# schematic.net
KiCad netlist of a schematic drawn in EAGLE
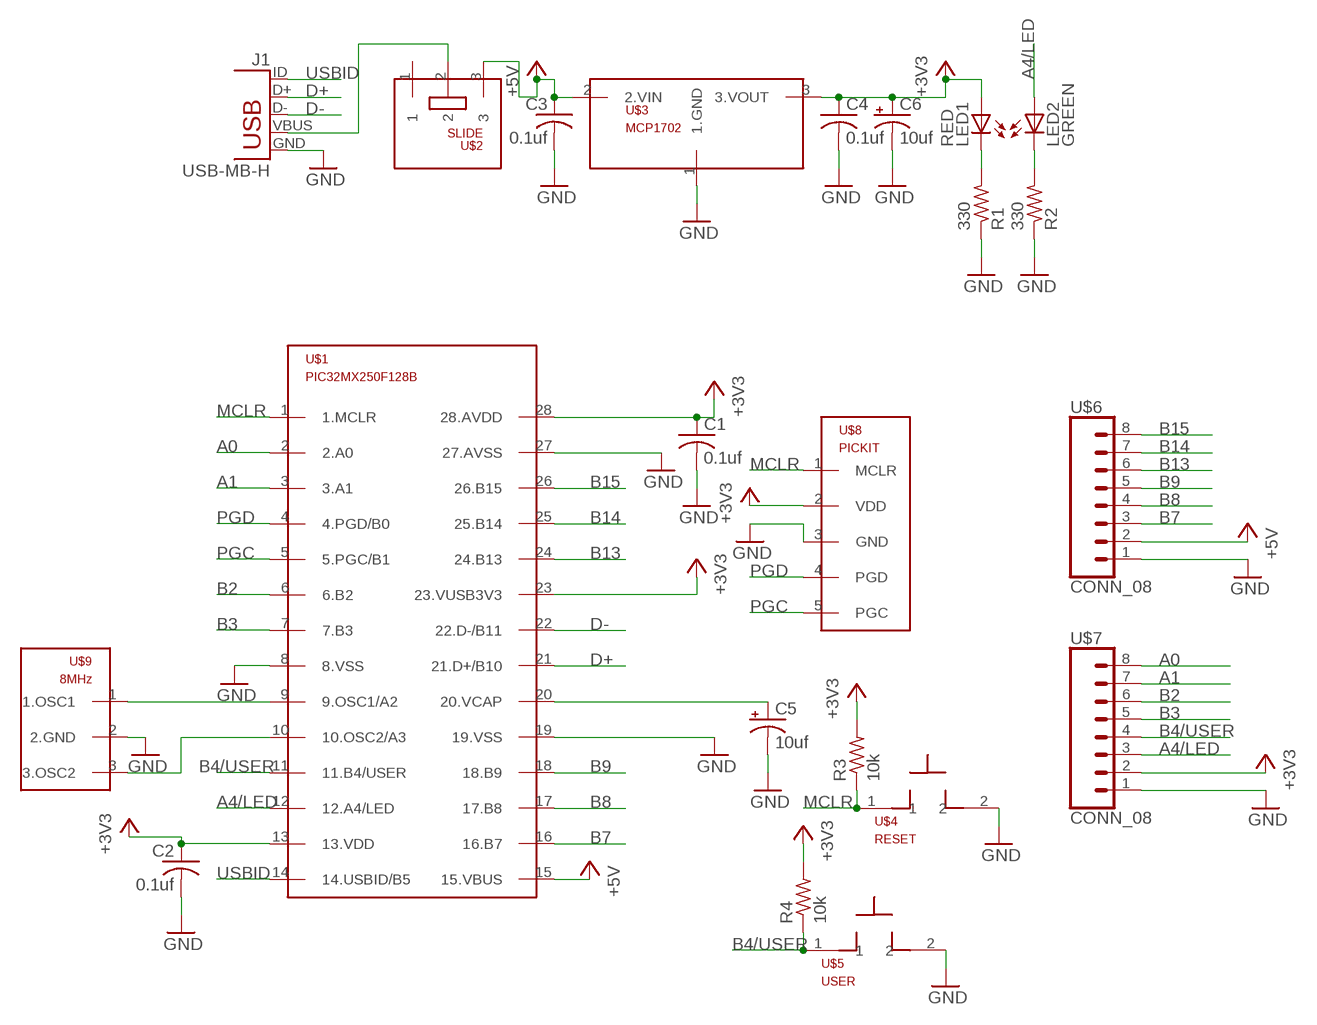
[diagram p0: schematic, sheet 1]

(export (version "E")
  (design (tool "Eeschema 10.0.6"))
  (components
    (comp (ref "C1")
      (value "0.1uf")
      (footprint "eagle-import:C025-025X050")
      (libsource (lib "eagle-import") (part "C-US025-025X050"))
    )
    (comp (ref "C2")
      (value "0.1uf")
      (footprint "eagle-import:C025-025X050")
      (libsource (lib "eagle-import") (part "C-US025-025X050"))
    )
    (comp (ref "C3")
      (value "0.1uf")
      (footprint "eagle-import:C025-025X050")
      (libsource (lib "eagle-import") (part "C-US025-025X050"))
    )
    (comp (ref "C4")
      (value "0.1uf")
      (footprint "eagle-import:C025-025X050")
      (libsource (lib "eagle-import") (part "C-US025-025X050"))
    )
    (comp (ref "C5")
      (value "10uf")
      (footprint "eagle-import:B45181B")
      (libsource (lib "eagle-import") (part "CPOL-USB45181B"))
    )
    (comp (ref "C6")
      (value "10uf")
      (footprint "eagle-import:B45181B")
      (libsource (lib "eagle-import") (part "CPOL-USB45181B"))
    )
    (comp (ref "J1")
      (value "USB-MB-H")
      (footprint "eagle-import:USB-MB-H")
      (libsource (lib "eagle-import") (part "USB-MB-H"))
    )
    (comp (ref "LED1")
      (value "RED")
      (footprint "eagle-import:LED3MM")
      (libsource (lib "eagle-import") (part "LED3MM"))
    )
    (comp (ref "LED2")
      (value "GREEN")
      (footprint "eagle-import:LED3MM")
      (libsource (lib "eagle-import") (part "LED3MM"))
    )
    (comp (ref "R1")
      (value "330")
      (footprint "eagle-import:0207_10")
      (libsource (lib "eagle-import") (part "R-US_0207/10"))
    )
    (comp (ref "R2")
      (value "330")
      (footprint "eagle-import:0207_10")
      (libsource (lib "eagle-import") (part "R-US_0207/10"))
    )
    (comp (ref "R3")
      (value "10k")
      (footprint "eagle-import:0207_10")
      (libsource (lib "eagle-import") (part "R-US_0207/10"))
    )
    (comp (ref "R4")
      (value "10k")
      (footprint "eagle-import:0207_10")
      (libsource (lib "eagle-import") (part "R-US_0207/10"))
    )
    (comp (ref "U$1")
      (value "PIC32MX250F128B")
      (footprint "eagle-import:DIL28-3")
      (libsource (lib "eagle-import") (part "PIC32MX250F128B"))
    )
    (comp (ref "U$2")
      (value "SLIDE")
      (footprint "eagle-import:SLIDE")
      (libsource (lib "eagle-import") (part "SLIDE"))
    )
    (comp (ref "U$3")
      (value "MCP1702")
      (footprint "eagle-import:TO92")
      (libsource (lib "eagle-import") (part "MCP1702"))
    )
    (comp (ref "U$4")
      (value "RESET")
      (footprint "eagle-import:PB")
      (libsource (lib "eagle-import") (part "PB"))
    )
    (comp (ref "U$5")
      (value "USER")
      (footprint "eagle-import:PB")
      (libsource (lib "eagle-import") (part "PB"))
    )
    (comp (ref "U$6")
      (value "CONN_08")
      (footprint "eagle-import:1X08")
      (libsource (lib "eagle-import") (part "CONN_08"))
    )
    (comp (ref "U$7")
      (value "CONN_08")
      (footprint "eagle-import:1X08")
      (libsource (lib "eagle-import") (part "CONN_08"))
    )
    (comp (ref "U$8")
      (value "PICKIT")
      (footprint "eagle-import:1X05")
      (libsource (lib "eagle-import") (part "PICKIT"))
    )
    (comp (ref "U$9")
      (value "8MHz")
      (footprint "eagle-import:OSC")
      (libsource (lib "eagle-import") (part "OSC"))
    )
  )
  (nets
    (net (code "1") (name "+3V3") (class "Default")
      (node (ref "C1") (pin "1") (pinfunction "1_1") (pintype "passive"))
      (node (ref "C2") (pin "1") (pinfunction "1_1") (pintype "passive"))
      (node (ref "C4") (pin "1") (pinfunction "1_1") (pintype "passive"))
      (node (ref "C6") (pin "+") (pinfunction "+_+") (pintype "passive"))
      (node (ref "LED1") (pin "A") (pinfunction "A_A") (pintype "passive"))
      (node (ref "R3") (pin "2") (pinfunction "2_2") (pintype "passive"))
      (node (ref "R4") (pin "2") (pinfunction "2_2") (pintype "passive"))
      (node (ref "U$1") (pin "13") (pinfunction "13.VDD_13") (pintype "bidirectional"))
      (node (ref "U$1") (pin "23") (pinfunction "23.VUSB3V3_23") (pintype "bidirectional"))
      (node (ref "U$1") (pin "28") (pinfunction "28.AVDD_28") (pintype "bidirectional"))
      (node (ref "U$3") (pin "3") (pinfunction "3.VOUT_3") (pintype "bidirectional"))
      (node (ref "U$7") (pin "2") (pinfunction "2_2") (pintype "passive"))
      (node (ref "U$8") (pin "2") (pinfunction "VDD_2") (pintype "bidirectional"))
    )
    (net (code "2") (name "+5V") (class "Default")
      (node (ref "C3") (pin "1") (pinfunction "1_1") (pintype "passive"))
      (node (ref "U$1") (pin "15") (pinfunction "15.VBUS_15") (pintype "bidirectional"))
      (node (ref "U$2") (pin "3") (pinfunction "3_3") (pintype "bidirectional"))
      (node (ref "U$3") (pin "2") (pinfunction "2.VIN_2") (pintype "bidirectional"))
      (node (ref "U$6") (pin "2") (pinfunction "2_2") (pintype "passive"))
    )
    (net (code "3") (name "/A0") (class "Default")
      (node (ref "U$1") (pin "2") (pinfunction "2.A0_2") (pintype "bidirectional"))
      (node (ref "U$7") (pin "8") (pinfunction "8_8") (pintype "passive"))
    )
    (net (code "4") (name "/A1") (class "Default")
      (node (ref "U$1") (pin "3") (pinfunction "3.A1_3") (pintype "bidirectional"))
      (node (ref "U$7") (pin "7") (pinfunction "7_7") (pintype "passive"))
    )
    (net (code "5") (name "/A4{slash}LED") (class "Default")
      (node (ref "LED2") (pin "A") (pinfunction "A_A") (pintype "passive"))
      (node (ref "U$1") (pin "12") (pinfunction "12.A4/LED_12") (pintype "bidirectional"))
      (node (ref "U$7") (pin "3") (pinfunction "3_3") (pintype "passive"))
    )
    (net (code "6") (name "/B2") (class "Default")
      (node (ref "U$1") (pin "6") (pinfunction "6.B2_6") (pintype "bidirectional"))
      (node (ref "U$7") (pin "6") (pinfunction "6_6") (pintype "passive"))
    )
    (net (code "7") (name "/B3") (class "Default")
      (node (ref "U$1") (pin "7") (pinfunction "7.B3_7") (pintype "bidirectional"))
      (node (ref "U$7") (pin "5") (pinfunction "5_5") (pintype "passive"))
    )
    (net (code "8") (name "/B4{slash}USER") (class "Default")
      (node (ref "R4") (pin "1") (pinfunction "1_1") (pintype "passive"))
      (node (ref "U$1") (pin "11") (pinfunction "11.B4/USER_11") (pintype "bidirectional"))
      (node (ref "U$5") (pin "1") (pinfunction "1_1") (pintype "bidirectional"))
      (node (ref "U$7") (pin "4") (pinfunction "4_4") (pintype "passive"))
    )
    (net (code "9") (name "/B7") (class "Default")
      (node (ref "U$1") (pin "16") (pinfunction "16.B7_16") (pintype "bidirectional"))
      (node (ref "U$6") (pin "3") (pinfunction "3_3") (pintype "passive"))
    )
    (net (code "10") (name "/B8") (class "Default")
      (node (ref "U$1") (pin "17") (pinfunction "17.B8_17") (pintype "bidirectional"))
      (node (ref "U$6") (pin "4") (pinfunction "4_4") (pintype "passive"))
    )
    (net (code "11") (name "/B9") (class "Default")
      (node (ref "U$1") (pin "18") (pinfunction "18.B9_18") (pintype "bidirectional"))
      (node (ref "U$6") (pin "5") (pinfunction "5_5") (pintype "passive"))
    )
    (net (code "12") (name "/B13") (class "Default")
      (node (ref "U$1") (pin "24") (pinfunction "24.B13_24") (pintype "bidirectional"))
      (node (ref "U$6") (pin "6") (pinfunction "6_6") (pintype "passive"))
    )
    (net (code "13") (name "/B14") (class "Default")
      (node (ref "U$1") (pin "25") (pinfunction "25.B14_25") (pintype "bidirectional"))
      (node (ref "U$6") (pin "7") (pinfunction "7_7") (pintype "passive"))
    )
    (net (code "14") (name "/B15") (class "Default")
      (node (ref "U$1") (pin "26") (pinfunction "26.B15_26") (pintype "bidirectional"))
      (node (ref "U$6") (pin "8") (pinfunction "8_8") (pintype "passive"))
    )
    (net (code "15") (name "/D+") (class "Default")
      (node (ref "J1") (pin "D+") (pinfunction "D+_D+") (pintype "bidirectional"))
      (node (ref "U$1") (pin "21") (pinfunction "21.D+/B10_21") (pintype "bidirectional"))
    )
    (net (code "16") (name "/D-") (class "Default")
      (node (ref "J1") (pin "D-") (pinfunction "D-_D-") (pintype "bidirectional"))
      (node (ref "U$1") (pin "22") (pinfunction "22.D-/B11_22") (pintype "bidirectional"))
    )
    (net (code "17") (name "/MCLR") (class "Default")
      (node (ref "R3") (pin "1") (pinfunction "1_1") (pintype "passive"))
      (node (ref "U$1") (pin "1") (pinfunction "1.MCLR_1") (pintype "bidirectional"))
      (node (ref "U$4") (pin "1") (pinfunction "1_1") (pintype "bidirectional"))
      (node (ref "U$8") (pin "1") (pinfunction "MCLR_1") (pintype "bidirectional"))
    )
    (net (code "18") (name "/PGC") (class "Default")
      (node (ref "U$1") (pin "5") (pinfunction "5.PGC/B1_5") (pintype "bidirectional"))
      (node (ref "U$8") (pin "5") (pinfunction "PGC_5") (pintype "bidirectional"))
    )
    (net (code "19") (name "/PGD") (class "Default")
      (node (ref "U$1") (pin "4") (pinfunction "4.PGD/B0_4") (pintype "bidirectional"))
      (node (ref "U$8") (pin "4") (pinfunction "PGD_4") (pintype "bidirectional"))
    )
    (net (code "20") (name "/USBID") (class "Default")
      (node (ref "J1") (pin "ID") (pinfunction "ID_ID") (pintype "bidirectional"))
      (node (ref "U$1") (pin "14") (pinfunction "14.USBID/B5_14") (pintype "bidirectional"))
    )
    (net (code "21") (name "GND") (class "Default")
      (node (ref "C1") (pin "2") (pinfunction "2_2") (pintype "passive"))
      (node (ref "C2") (pin "2") (pinfunction "2_2") (pintype "passive"))
      (node (ref "C3") (pin "2") (pinfunction "2_2") (pintype "passive"))
      (node (ref "C4") (pin "2") (pinfunction "2_2") (pintype "passive"))
      (node (ref "C5") (pin "-") (pinfunction "-_-") (pintype "passive"))
      (node (ref "C6") (pin "-") (pinfunction "-_-") (pintype "passive"))
      (node (ref "J1") (pin "GND") (pinfunction "GND_GND") (pintype "bidirectional"))
      (node (ref "R1") (pin "1") (pinfunction "1_1") (pintype "passive"))
      (node (ref "R2") (pin "1") (pinfunction "1_1") (pintype "passive"))
      (node (ref "U$1") (pin "19") (pinfunction "19.VSS_19") (pintype "bidirectional"))
      (node (ref "U$1") (pin "27") (pinfunction "27.AVSS_27") (pintype "bidirectional"))
      (node (ref "U$1") (pin "8") (pinfunction "8.VSS_8") (pintype "bidirectional"))
      (node (ref "U$3") (pin "1") (pinfunction "1.GND_1") (pintype "bidirectional"))
      (node (ref "U$4") (pin "2") (pinfunction "2_2") (pintype "bidirectional"))
      (node (ref "U$5") (pin "2") (pinfunction "2_2") (pintype "bidirectional"))
      (node (ref "U$6") (pin "1") (pinfunction "1_1") (pintype "passive"))
      (node (ref "U$7") (pin "1") (pinfunction "1_1") (pintype "passive"))
      (node (ref "U$8") (pin "3") (pinfunction "GND_3") (pintype "bidirectional"))
      (node (ref "U$9") (pin "2") (pinfunction "2.GND_2") (pintype "bidirectional"))
    )
    (net (code "22") (name "Net-(J1-PadVBUS)") (class "Default")
      (node (ref "J1") (pin "VBUS") (pinfunction "VBUS_VBUS") (pintype "bidirectional"))
      (node (ref "U$2") (pin "2") (pinfunction "2_2") (pintype "bidirectional"))
    )
    (net (code "23") (name "Net-(LED1-C)") (class "Default")
      (node (ref "LED1") (pin "K") (pinfunction "C_K") (pintype "passive"))
      (node (ref "R1") (pin "2") (pinfunction "2_2") (pintype "passive"))
    )
    (net (code "24") (name "Net-(LED2-C)") (class "Default")
      (node (ref "LED2") (pin "K") (pinfunction "C_K") (pintype "passive"))
      (node (ref "R2") (pin "2") (pinfunction "2_2") (pintype "passive"))
    )
    (net (code "25") (name "Net-(U$1-9.OSC1{slash}A2)") (class "Default")
      (node (ref "U$1") (pin "9") (pinfunction "9.OSC1/A2_9") (pintype "bidirectional"))
      (node (ref "U$9") (pin "1") (pinfunction "1.OSC1_1") (pintype "bidirectional"))
    )
    (net (code "26") (name "Net-(U$1-10.OSC2{slash}A3)") (class "Default")
      (node (ref "U$1") (pin "10") (pinfunction "10.OSC2/A3_10") (pintype "bidirectional"))
      (node (ref "U$9") (pin "3") (pinfunction "3.OSC2_3") (pintype "bidirectional"))
    )
    (net (code "27") (name "Net-(U$1-20.VCAP)") (class "Default")
      (node (ref "C5") (pin "+") (pinfunction "+_+") (pintype "passive"))
      (node (ref "U$1") (pin "20") (pinfunction "20.VCAP_20") (pintype "bidirectional"))
    )
    (net (code "28") (name "unconnected-(U$2-Pad1)") (class "Default")
      (node (ref "U$2") (pin "1") (pinfunction "1_1") (pintype "bidirectional"))
    )
  )
)
